# Power-Board.net
KiCad netlist of a schematic drawn in EAGLE
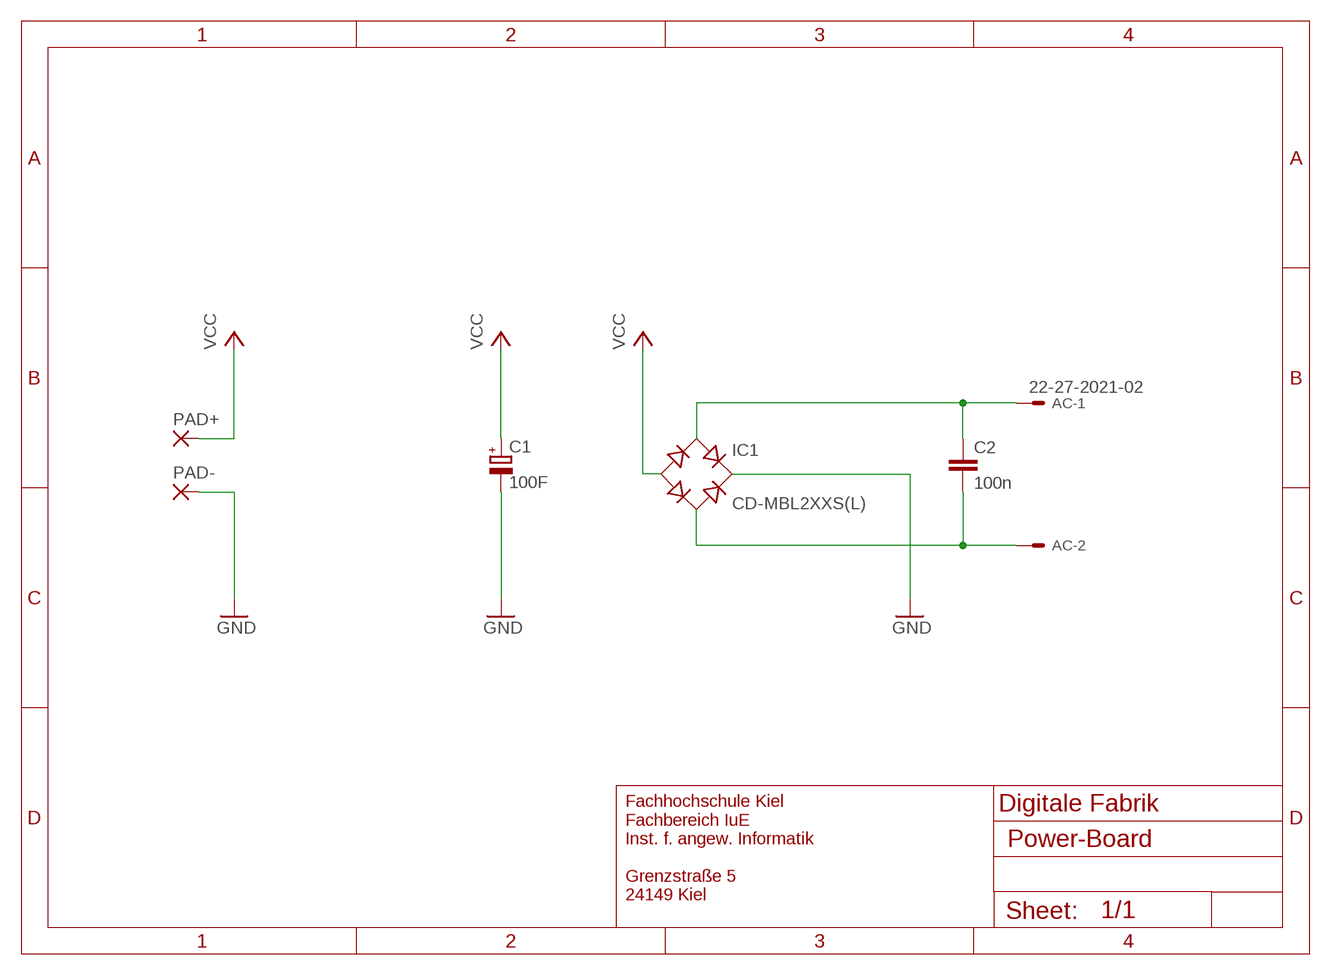
[diagram p0: schematic, sheet 1]

(export (version "E")
  (design (tool "Eeschema 10.0.6"))
  (components
    (comp (ref "AC")
      (value "22-27-2021-02")
      (footprint "eagle-import:6410-02")
      (libsource (lib "eagle-import") (part "22-?-0227-2021"))
    )
    (comp (ref "C1")
      (value "100F")
      (footprint "eagle-import:E7,5-18,5")
      (libsource (lib "eagle-import") (part "CPOL-EUE7,5-18,5"))
    )
    (comp (ref "C2")
      (value "100n")
      (footprint "eagle-import:C0805K")
      (libsource (lib "eagle-import") (part "C-EUC0805K"))
    )
    (comp (ref "IC1")
      (value "CD-MBL2XXS(L)")
      (footprint "eagle-import:CD-MBL2XXS(L)")
      (libsource (lib "eagle-import") (part "CD-MBL2XXS(L)"))
    )
    (comp (ref "PAD+")
      (value "WIREPAD4,16O1,6")
      (footprint "eagle-import:4,16O1,6")
      (libsource (lib "eagle-import") (part "WIREPAD4,16O1,6"))
    )
    (comp (ref "PAD-")
      (value "WIREPAD4,16O1,6")
      (footprint "eagle-import:4,16O1,6")
      (libsource (lib "eagle-import") (part "WIREPAD4,16O1,6"))
    )
  )
  (nets
    (net (code "1") (name "GND") (class "Default")
      (node (ref "C1") (pin "-") (pinfunction "-_-") (pintype "passive"))
      (node (ref "IC1") (pin "DC+") (pinfunction "+_DC+") (pintype "passive"))
      (node (ref "PAD-") (pin "1") (pinfunction "P_1") (pintype "passive"))
    )
    (net (code "2") (name "Net-(ACA-S)") (class "Default")
      (node (ref "AC") (pin "1") (pinfunction "S_1") (pintype "passive"))
      (node (ref "C2") (pin "1") (pinfunction "1_1") (pintype "passive"))
      (node (ref "IC1") (pin "AC1") (pinfunction "AC1_AC1") (pintype "passive"))
    )
    (net (code "3") (name "Net-(ACB-S)") (class "Default")
      (node (ref "AC") (pin "2") (pinfunction "S_2") (pintype "passive"))
      (node (ref "C2") (pin "2") (pinfunction "2_2") (pintype "passive"))
      (node (ref "IC1") (pin "AC2") (pinfunction "AC2_AC2") (pintype "passive"))
    )
    (net (code "4") (name "VCC") (class "Default")
      (node (ref "C1") (pin "+") (pinfunction "+_+") (pintype "passive"))
      (node (ref "IC1") (pin "DC-") (pinfunction "-_DC-") (pintype "passive"))
      (node (ref "PAD+") (pin "1") (pinfunction "P_1") (pintype "passive"))
    )
  )
)
